# SCH_fl-test_2024-12-06.net
KiCad netlist of a schematic drawn in EasyEDA
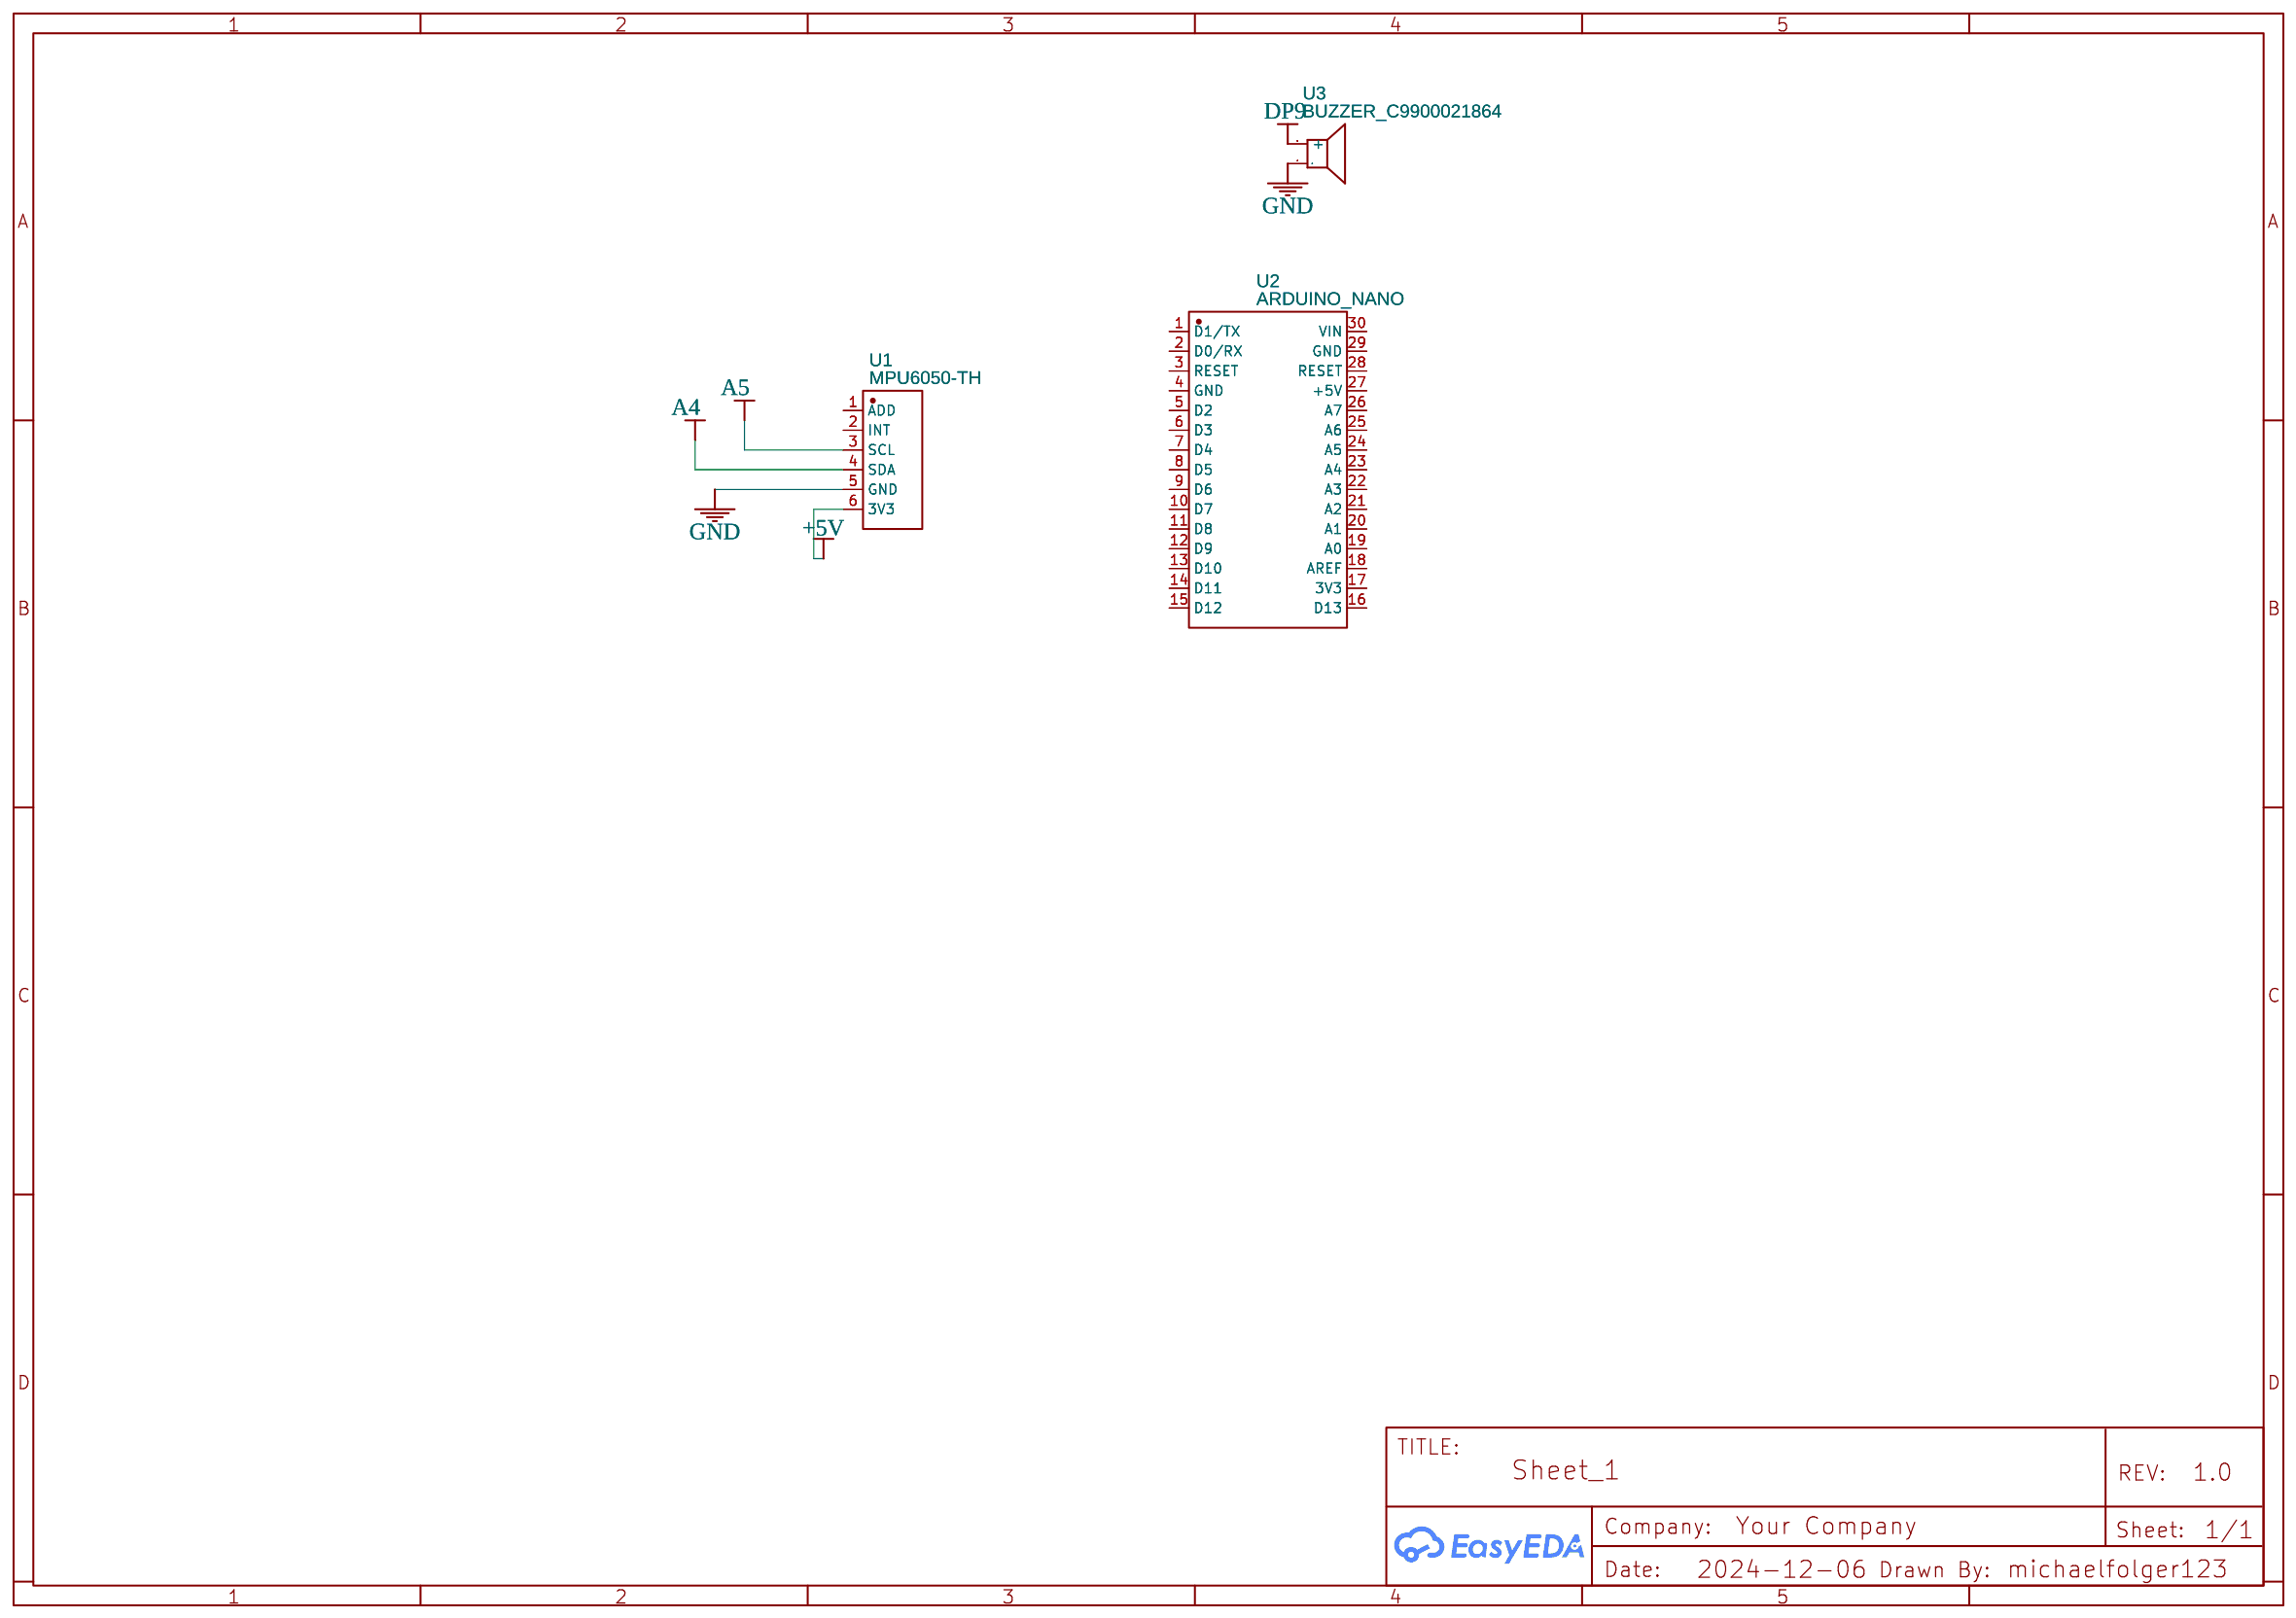
[diagram p0: schematic sheet]

(export (version "E")
  (design (tool "Eeschema 10.0.6"))
  (components
    (comp (ref "U1") (value "MPU6050-TH") (libsource (lib "") (part "MPU6050-TH")))
    (comp (ref "U2") (value "ARDUINO_NANO") (libsource (lib "") (part "ARDUINO_NANO")))
    (comp (ref "U3")
      (value "BUZZER_C9900021864")
      (fields (field (name "Manufacturer Part") "BUZZER"))
      (libsource (lib "") (part "BUZZER_C9900021864"))
    )
  )
  (nets
    (net (code "1") (name "+5V") (class "Default")
      (node (ref "U1") (pin "6") (pinfunction "3V3_6") (pintype "unspecified"))
    )
    (net (code "2") (name "A4") (class "Default")
      (node (ref "U1") (pin "4") (pinfunction "SDA_4") (pintype "unspecified"))
    )
    (net (code "3") (name "A5") (class "Default")
      (node (ref "U1") (pin "3") (pinfunction "SCL_3") (pintype "unspecified"))
    )
    (net (code "4") (name "DP9") (class "Default")
      (node (ref "U3") (pin "2") (pinfunction "+_2") (pintype "unspecified"))
    )
    (net (code "5") (name "GND") (class "Default")
      (node (ref "U1") (pin "5") (pinfunction "GND_5") (pintype "unspecified"))
      (node (ref "U3") (pin "1") (pinfunction "1_1") (pintype "unspecified"))
    )
    (net (code "6") (name "unconnected-(U1-ADD-Pad1)") (class "Default")
      (node (ref "U1") (pin "1") (pinfunction "ADD_1") (pintype "unspecified"))
    )
    (net (code "7") (name "unconnected-(U1-INT-Pad2)") (class "Default")
      (node (ref "U1") (pin "2") (pinfunction "INT_2") (pintype "unspecified"))
    )
    (net (code "8") (name "unconnected-(U2-+5V-Pad27)") (class "Default")
      (node (ref "U2") (pin "27") (pinfunction "+5V_27") (pintype "unspecified"))
    )
    (net (code "9") (name "unconnected-(U2-3V3-Pad17)") (class "Default")
      (node (ref "U2") (pin "17") (pinfunction "3V3_17") (pintype "unspecified"))
    )
    (net (code "10") (name "unconnected-(U2-A0-Pad19)") (class "Default")
      (node (ref "U2") (pin "19") (pinfunction "A0_19") (pintype "unspecified"))
    )
    (net (code "11") (name "unconnected-(U2-A1-Pad20)") (class "Default")
      (node (ref "U2") (pin "20") (pinfunction "A1_20") (pintype "unspecified"))
    )
    (net (code "12") (name "unconnected-(U2-A2-Pad21)") (class "Default")
      (node (ref "U2") (pin "21") (pinfunction "A2_21") (pintype "unspecified"))
    )
    (net (code "13") (name "unconnected-(U2-A3-Pad22)") (class "Default")
      (node (ref "U2") (pin "22") (pinfunction "A3_22") (pintype "unspecified"))
    )
    (net (code "14") (name "unconnected-(U2-A4-Pad23)") (class "Default")
      (node (ref "U2") (pin "23") (pinfunction "A4_23") (pintype "unspecified"))
    )
    (net (code "15") (name "unconnected-(U2-A5-Pad24)") (class "Default")
      (node (ref "U2") (pin "24") (pinfunction "A5_24") (pintype "unspecified"))
    )
    (net (code "16") (name "unconnected-(U2-A6-Pad25)") (class "Default")
      (node (ref "U2") (pin "25") (pinfunction "A6_25") (pintype "unspecified"))
    )
    (net (code "17") (name "unconnected-(U2-A7-Pad26)") (class "Default")
      (node (ref "U2") (pin "26") (pinfunction "A7_26") (pintype "unspecified"))
    )
    (net (code "18") (name "unconnected-(U2-AREF-Pad18)") (class "Default")
      (node (ref "U2") (pin "18") (pinfunction "AREF_18") (pintype "unspecified"))
    )
    (net (code "19") (name "unconnected-(U2-D0{slash}RX-Pad2)") (class "Default")
      (node (ref "U2") (pin "2") (pinfunction "D0/RX_2") (pintype "unspecified"))
    )
    (net (code "20") (name "unconnected-(U2-D1{slash}TX-Pad1)") (class "Default")
      (node (ref "U2") (pin "1") (pinfunction "D1/TX_1") (pintype "unspecified"))
    )
    (net (code "21") (name "unconnected-(U2-D2-Pad5)") (class "Default")
      (node (ref "U2") (pin "5") (pinfunction "D2_5") (pintype "unspecified"))
    )
    (net (code "22") (name "unconnected-(U2-D3-Pad6)") (class "Default")
      (node (ref "U2") (pin "6") (pinfunction "D3_6") (pintype "unspecified"))
    )
    (net (code "23") (name "unconnected-(U2-D4-Pad7)") (class "Default")
      (node (ref "U2") (pin "7") (pinfunction "D4_7") (pintype "unspecified"))
    )
    (net (code "24") (name "unconnected-(U2-D5-Pad8)") (class "Default")
      (node (ref "U2") (pin "8") (pinfunction "D5_8") (pintype "unspecified"))
    )
    (net (code "25") (name "unconnected-(U2-D6-Pad9)") (class "Default")
      (node (ref "U2") (pin "9") (pinfunction "D6_9") (pintype "unspecified"))
    )
    (net (code "26") (name "unconnected-(U2-D7-Pad10)") (class "Default")
      (node (ref "U2") (pin "10") (pinfunction "D7_10") (pintype "unspecified"))
    )
    (net (code "27") (name "unconnected-(U2-D8-Pad11)") (class "Default")
      (node (ref "U2") (pin "11") (pinfunction "D8_11") (pintype "unspecified"))
    )
    (net (code "28") (name "unconnected-(U2-D9-Pad12)") (class "Default")
      (node (ref "U2") (pin "12") (pinfunction "D9_12") (pintype "unspecified"))
    )
    (net (code "29") (name "unconnected-(U2-D10-Pad13)") (class "Default")
      (node (ref "U2") (pin "13") (pinfunction "D10_13") (pintype "unspecified"))
    )
    (net (code "30") (name "unconnected-(U2-D11-Pad14)") (class "Default")
      (node (ref "U2") (pin "14") (pinfunction "D11_14") (pintype "unspecified"))
    )
    (net (code "31") (name "unconnected-(U2-D12-Pad15)") (class "Default")
      (node (ref "U2") (pin "15") (pinfunction "D12_15") (pintype "unspecified"))
    )
    (net (code "32") (name "unconnected-(U2-D13-Pad16)") (class "Default")
      (node (ref "U2") (pin "16") (pinfunction "D13_16") (pintype "unspecified"))
    )
    (net (code "33") (name "unconnected-(U2-GND-Pad4)") (class "Default")
      (node (ref "U2") (pin "4") (pinfunction "GND_4") (pintype "unspecified"))
    )
    (net (code "34") (name "unconnected-(U2-GND-Pad29)") (class "Default")
      (node (ref "U2") (pin "29") (pinfunction "GND_29") (pintype "unspecified"))
    )
    (net (code "35") (name "unconnected-(U2-RESET-Pad3)") (class "Default")
      (node (ref "U2") (pin "3") (pinfunction "RESET_3") (pintype "unspecified"))
    )
    (net (code "36") (name "unconnected-(U2-RESET-Pad28)") (class "Default")
      (node (ref "U2") (pin "28") (pinfunction "RESET_28") (pintype "unspecified"))
    )
    (net (code "37") (name "unconnected-(U2-VIN-Pad30)") (class "Default")
      (node (ref "U2") (pin "30") (pinfunction "VIN_30") (pintype "unspecified"))
    )
  )
)
